# tps61040-boost-driver-mk-1_0.net
KiCad netlist of a schematic drawn in EAGLE
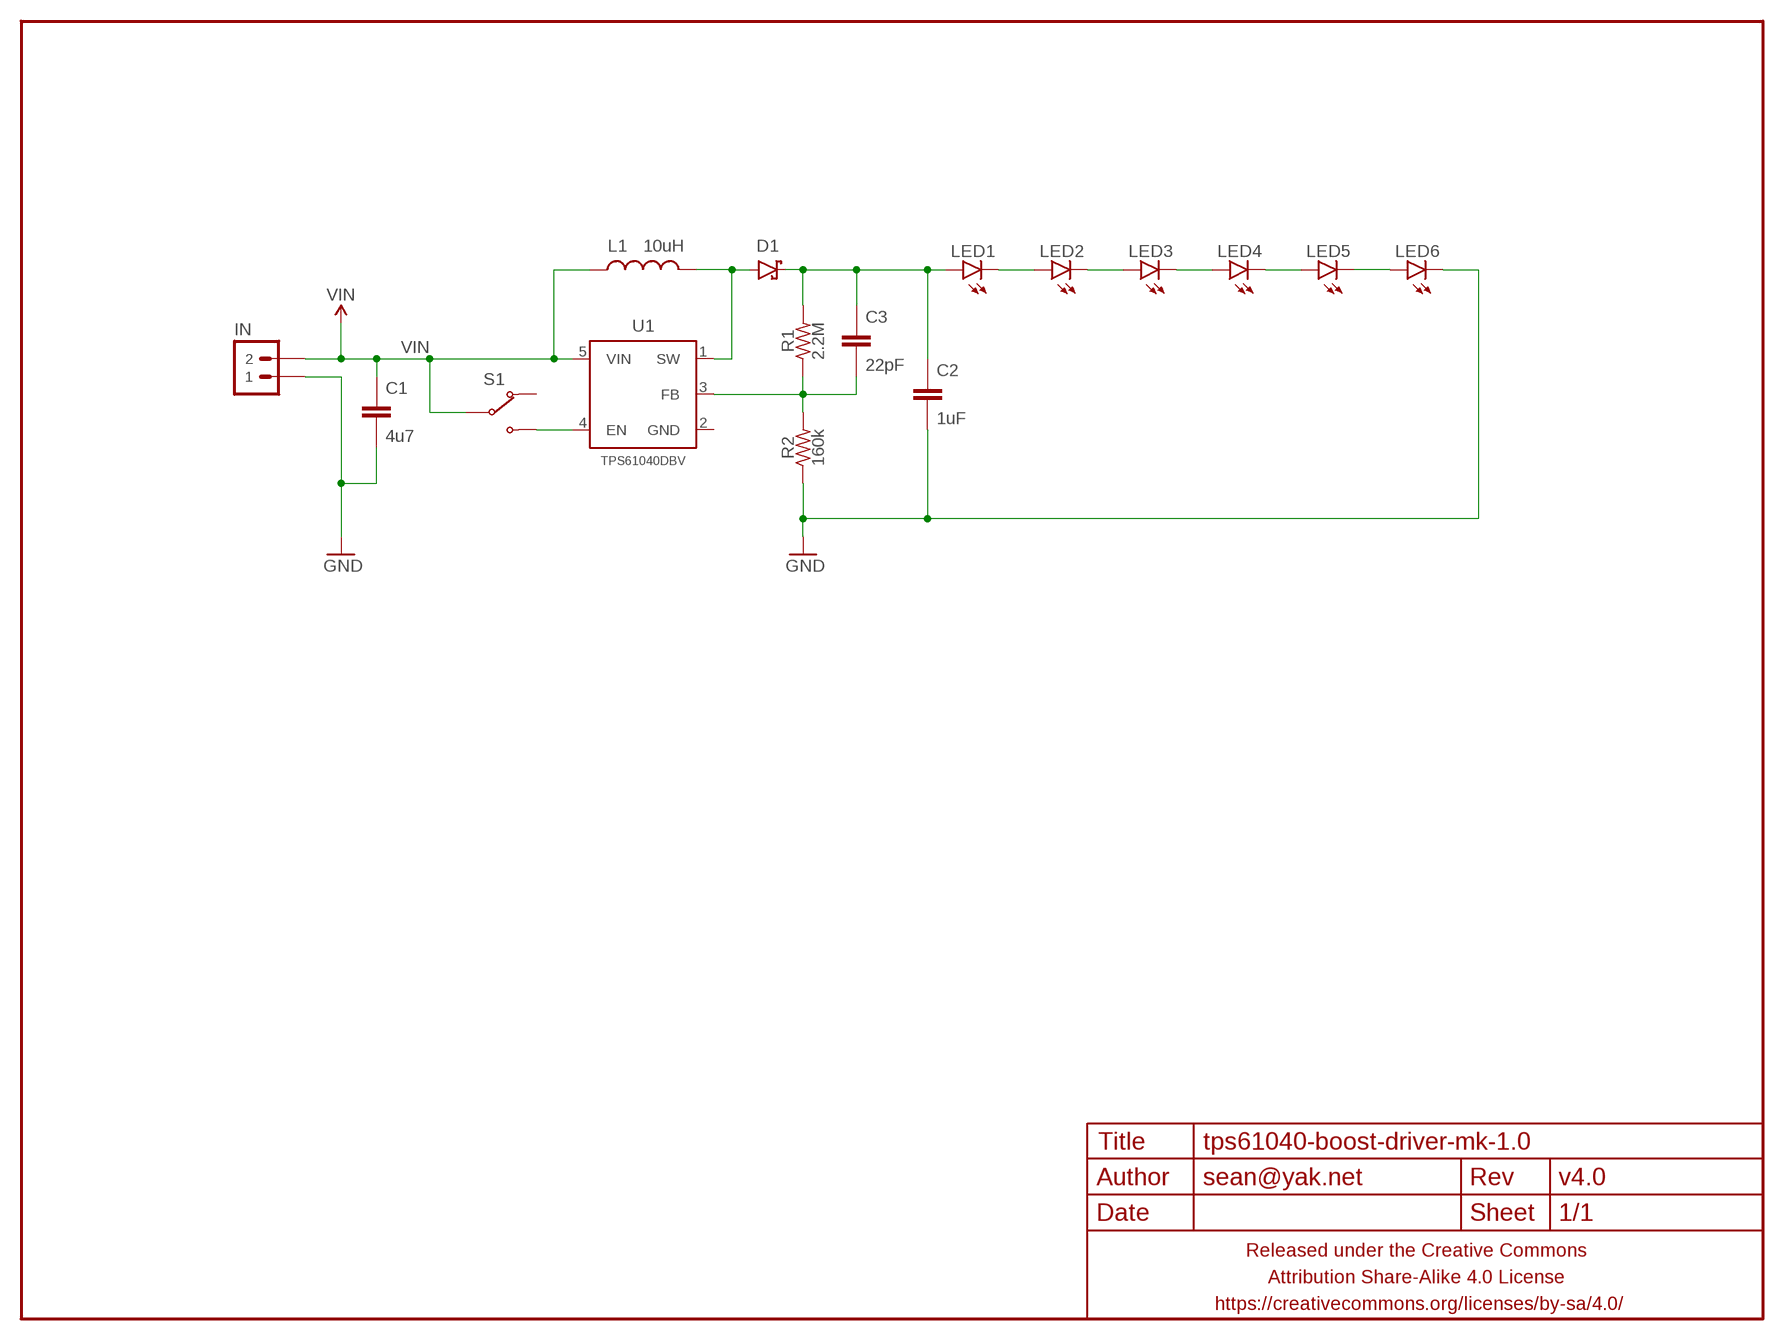
[diagram p0: schematic, sheet 1]

(export (version "E")
  (design (tool "Eeschema 10.0.6"))
  (components
    (comp (ref "C1")
      (value "4u7")
      (footprint "eagle-import:C0603-TIGHTER")
      (libsource (lib "eagle-import") (part "CAPACITOR-CERAMICC0603-TIGHTER"))
    )
    (comp (ref "C2")
      (value "1uF")
      (footprint "eagle-import:C0603-TIGHTER")
      (libsource (lib "eagle-import") (part "CAPACITOR-CERAMICC0603-TIGHTER"))
    )
    (comp (ref "C3")
      (value "22pF")
      (footprint "eagle-import:C0603-TIGHTER")
      (libsource (lib "eagle-import") (part "CAPACITOR-CERAMICC0603-TIGHTER"))
    )
    (comp (ref "D1")
      (value "DIODE-SCHOTTKYSOD123")
      (footprint "eagle-import:SOD123-SCHOTTKY")
      (libsource (lib "eagle-import") (part "DIODE-SCHOTTKYSOD123"))
    )
    (comp (ref "FRAME1")
      (value "FRAME-LETTERNO_PACKAGE")
      (footprint "eagle-import:DUMMY")
      (fields (field (name "DESIGNER") "sean@yak.net") (field (name "VERSION") "v4.0"))
      (libsource (lib "eagle-import") (part "FRAME-LETTERNO_PACKAGE"))
    )
    (comp (ref "IN")
      (value "M02PTH-CENTERED-R+")
      (footprint "eagle-import:1X02-CENTER-R+")
      (libsource (lib "eagle-import") (part "M02PTH-CENTERED-R+"))
    )
    (comp (ref "L1")
      (value "10uH")
      (footprint "eagle-import:L0603")
      (libsource (lib "eagle-import") (part "INDUCTOR0603-TIGHTER"))
    )
    (comp (ref "LED1")
      (value "LED5MM_SHORTPADS")
      (footprint "eagle-import:LED5MM_SHORTPADS")
      (libsource (lib "eagle-import") (part "LED5MM_SHORTPADS"))
    )
    (comp (ref "LED2")
      (value "LED5MM_SHORTPADS")
      (footprint "eagle-import:LED5MM_SHORTPADS")
      (libsource (lib "eagle-import") (part "LED5MM_SHORTPADS"))
    )
    (comp (ref "LED3")
      (value "LED5MM_SHORTPADS")
      (footprint "eagle-import:LED5MM_SHORTPADS")
      (libsource (lib "eagle-import") (part "LED5MM_SHORTPADS"))
    )
    (comp (ref "LED4")
      (value "LED5MM_SHORTPADS")
      (footprint "eagle-import:LED5MM_SHORTPADS")
      (libsource (lib "eagle-import") (part "LED5MM_SHORTPADS"))
    )
    (comp (ref "LED5")
      (value "LED5MM_SHORTPADS")
      (footprint "eagle-import:LED5MM_SHORTPADS")
      (libsource (lib "eagle-import") (part "LED5MM_SHORTPADS"))
    )
    (comp (ref "LED6")
      (value "LED5MM_SHORTPADS")
      (footprint "eagle-import:LED5MM_SHORTPADS")
      (libsource (lib "eagle-import") (part "LED5MM_SHORTPADS"))
    )
    (comp (ref "R1")
      (value "2.2M")
      (footprint "eagle-import:R0603-TIGHTER")
      (libsource (lib "eagle-import") (part "RESISTORR0603-TIGHTER"))
    )
    (comp (ref "R2")
      (value "160k")
      (footprint "eagle-import:R0603-TIGHTER")
      (libsource (lib "eagle-import") (part "RESISTORR0603-TIGHTER"))
    )
    (comp (ref "S1")
      (value "SWITCH-SPDTSMD-RA")
      (footprint "eagle-import:SWITCH-SPDT-SMD-RA")
      (libsource (lib "eagle-import") (part "SWITCH-SPDTSMD-RA"))
    )
    (comp (ref "U1")
      (value "TPS61040DBV")
      (footprint "eagle-import:SOT23-5")
      (libsource (lib "eagle-import") (part "TPS61040DBV"))
    )
  )
  (nets
    (net (code "1") (name "GND") (class "Default")
      (node (ref "C1") (pin "2") (pinfunction "2_2") (pintype "passive"))
      (node (ref "C2") (pin "2") (pinfunction "2_2") (pintype "passive"))
      (node (ref "IN") (pin "1") (pinfunction "1_1") (pintype "passive"))
      (node (ref "LED6") (pin "K") (pinfunction "C_K") (pintype "passive"))
      (node (ref "R2") (pin "1") (pinfunction "1_1") (pintype "passive"))
    )
    (net (code "2") (name "Net-(C2-Pad1)") (class "Default")
      (node (ref "C2") (pin "1") (pinfunction "1_1") (pintype "passive"))
      (node (ref "C3") (pin "1") (pinfunction "1_1") (pintype "passive"))
      (node (ref "D1") (pin "C") (pinfunction "C_C") (pintype "passive"))
      (node (ref "LED1") (pin "A") (pinfunction "A_A") (pintype "passive"))
      (node (ref "R1") (pin "2") (pinfunction "2_2") (pintype "passive"))
    )
    (net (code "3") (name "Net-(LED1-C)") (class "Default")
      (node (ref "LED1") (pin "K") (pinfunction "C_K") (pintype "passive"))
      (node (ref "LED2") (pin "A") (pinfunction "A_A") (pintype "passive"))
    )
    (net (code "4") (name "Net-(LED2-C)") (class "Default")
      (node (ref "LED2") (pin "K") (pinfunction "C_K") (pintype "passive"))
      (node (ref "LED3") (pin "A") (pinfunction "A_A") (pintype "passive"))
    )
    (net (code "5") (name "Net-(LED3-C)") (class "Default")
      (node (ref "LED3") (pin "K") (pinfunction "C_K") (pintype "passive"))
      (node (ref "LED4") (pin "A") (pinfunction "A_A") (pintype "passive"))
    )
    (net (code "6") (name "Net-(LED4-C)") (class "Default")
      (node (ref "LED4") (pin "K") (pinfunction "C_K") (pintype "passive"))
      (node (ref "LED5") (pin "A") (pinfunction "A_A") (pintype "passive"))
    )
    (net (code "7") (name "Net-(LED5-C)") (class "Default")
      (node (ref "LED5") (pin "K") (pinfunction "C_K") (pintype "passive"))
      (node (ref "LED6") (pin "A") (pinfunction "A_A") (pintype "passive"))
    )
    (net (code "8") (name "Net-(S1-NO)") (class "Default")
      (node (ref "S1") (pin "1") (pinfunction "NO_1") (pintype "passive"))
      (node (ref "U1") (pin "4") (pinfunction "EN_4") (pintype "bidirectional"))
    )
    (net (code "9") (name "Net-(U1-FB)") (class "Default")
      (node (ref "C3") (pin "2") (pinfunction "2_2") (pintype "passive"))
      (node (ref "R1") (pin "1") (pinfunction "1_1") (pintype "passive"))
      (node (ref "R2") (pin "2") (pinfunction "2_2") (pintype "passive"))
      (node (ref "U1") (pin "3") (pinfunction "FB_3") (pintype "bidirectional"))
    )
    (net (code "10") (name "Net-(U1-SW)") (class "Default")
      (node (ref "D1") (pin "A") (pinfunction "A_A") (pintype "passive"))
      (node (ref "L1") (pin "2") (pinfunction "2_2") (pintype "passive"))
      (node (ref "U1") (pin "1") (pinfunction "SW_1") (pintype "bidirectional"))
    )
    (net (code "11") (name "VIN") (class "Default")
      (node (ref "C1") (pin "1") (pinfunction "1_1") (pintype "passive"))
      (node (ref "IN") (pin "2") (pinfunction "2_2") (pintype "passive"))
      (node (ref "L1") (pin "1") (pinfunction "1_1") (pintype "passive"))
      (node (ref "S1") (pin "2") (pinfunction "COM_2") (pintype "passive"))
      (node (ref "U1") (pin "5") (pinfunction "VIN_5") (pintype "bidirectional"))
    )
    (net (code "12") (name "unconnected-(S1-NC-Pad3)") (class "Default")
      (node (ref "S1") (pin "3") (pinfunction "NC_3") (pintype "passive"))
    )
    (net (code "13") (name "unconnected-(U1-GND-Pad2)") (class "Default")
      (node (ref "U1") (pin "2") (pinfunction "GND_2") (pintype "bidirectional"))
    )
  )
)
